# Deckelplatine_v090.net
KiCad netlist of a schematic drawn in EAGLE
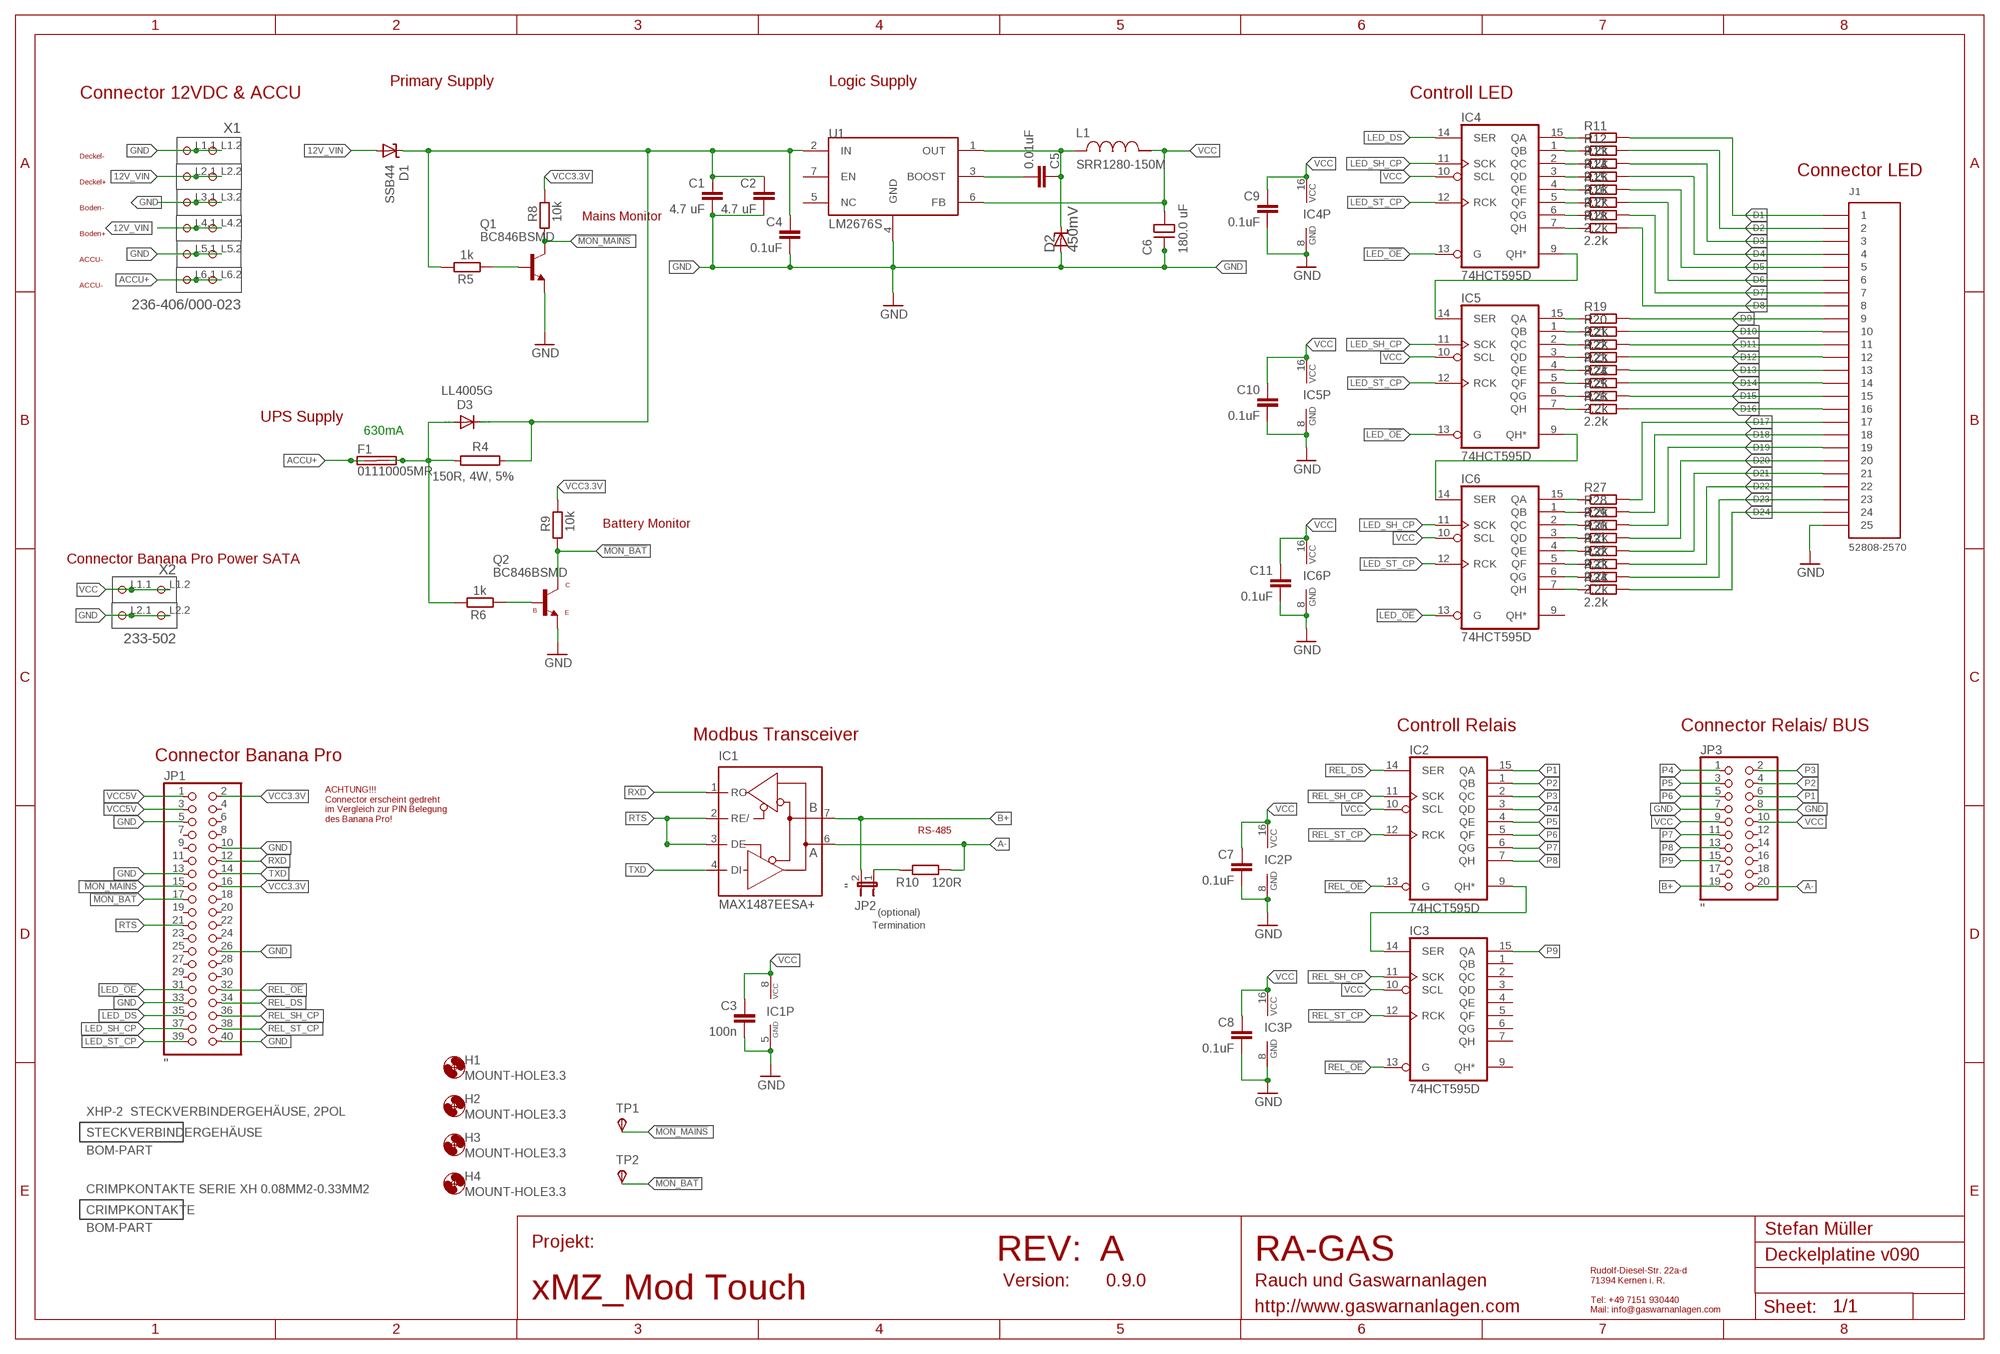
[diagram p0: schematic, sheet 1]

(export (version "E")
  (design (tool "Eeschema 10.0.6"))
  (components
    (comp (ref "C1")
      (value "4.7 uF")
      (footprint "eagle-import:GRM21BR61E475MA12L")
      (fields (field (name "MANUFACTURER_PART_NUMBER") "GRM21BR61E475MA12L") (field (name "MF") "MURATA"))
      (libsource (lib "eagle-import") (part "GRM21BR61E475MA12L"))
    )
    (comp (ref "C2")
      (value "4.7 uF")
      (footprint "eagle-import:GRM21BR61E475MA12L")
      (fields (field (name "MANUFACTURER_PART_NUMBER") "GRM21BR61E475MA12L") (field (name "MF") "MURATA"))
      (libsource (lib "eagle-import") (part "GRM21BR61E475MA12L"))
    )
    (comp (ref "C3")
      (value "100n")
      (footprint "eagle-import:C0603")
      (fields
        (field (name "MF") "KEMET")
        (field (name "MPN") "C0603C104K8RACTU")
        (field (name "PARTNO") "ECHU-16-100N")
      )
      (libsource (lib "eagle-import") (part "C-EUC0603"))
    )
    (comp (ref "C4")
      (value "0.1uF")
      (footprint "eagle-import:0805")
      (fields (field (name "MANUFACTURER_PART_NUMBER") "08053C104KAT2A") (field (name "MF") "AVX"))
      (libsource (lib "eagle-import") (part "08053C104KAT2A"))
    )
    (comp (ref "C5")
      (value "0.01uF")
      (footprint "eagle-import:GRM216R71H103KA01D")
      (fields (field (name "MANUFACTURER_PART_NUMBER") "GRM216R71H103KA01D") (field (name "MF") "MURATA"))
      (libsource (lib "eagle-import") (part "GRM216R71H103KA01D"))
    )
    (comp (ref "C6")
      (value "180.0 uF")
      (footprint "eagle-import:SM_RADIAL_10MM")
      (fields
        (field (name "MF") "PANASONIC ELECTRONIC COMPONENTS")
        (field (name "MPN") "16SVP180MX")
        (field (name "PARTNO") "RAD FC 560/35")
      )
      (libsource (lib "eagle-import") (part "16SVP180MSM_RADIAL_10MM"))
    )
    (comp (ref "C7")
      (value "0.1uF")
      (footprint "eagle-import:C0603")
      (fields
        (field (name "MF") "KEMET")
        (field (name "MPN") "C0603C104K8RACTU")
        (field (name "PARTNO") "SMD TAN.0,1/35")
      )
      (libsource (lib "eagle-import") (part "C-EUC0603"))
    )
    (comp (ref "C8")
      (value "0.1uF")
      (footprint "eagle-import:C0603")
      (fields
        (field (name "MF") "KEMET")
        (field (name "MPN") "C0603C104K8RACTU")
        (field (name "PARTNO") "SMD TAN.0,1/35")
      )
      (libsource (lib "eagle-import") (part "C-EUC0603"))
    )
    (comp (ref "C9")
      (value "0.1uF")
      (footprint "eagle-import:C0603")
      (fields
        (field (name "MF") "KEMET")
        (field (name "MPN") "C0603C104K8RACTU")
        (field (name "PARTNO") "SMD TAN.0,1/35")
      )
      (libsource (lib "eagle-import") (part "C-EUC0603"))
    )
    (comp (ref "C10")
      (value "0.1uF")
      (footprint "eagle-import:C0603")
      (fields
        (field (name "MF") "KEMET")
        (field (name "MPN") "C0603C104K8RACTU")
        (field (name "PARTNO") "SMD TAN.0,1/35")
      )
      (libsource (lib "eagle-import") (part "C-EUC0603"))
    )
    (comp (ref "C11")
      (value "0.1uF")
      (footprint "eagle-import:C0603")
      (fields
        (field (name "MF") "KEMET")
        (field (name "MPN") "C0603C104K8RACTU")
        (field (name "PARTNO") "SMD TAN.0,1/35")
      )
      (libsource (lib "eagle-import") (part "C-EUC0603"))
    )
    (comp (ref "D1")
      (value "SSB44")
      (footprint "eagle-import:SMBJ")
      (fields (field (name "MF") "VISHAY") (field (name "MPN") "SSB44-E3/52T"))
      (libsource (lib "eagle-import") (part "SUPPRESSOR-SMBJ"))
    )
    (comp (ref "D2")
      (value "450mV")
      (footprint "eagle-import:SMB")
      (fields (field (name "MANUFACTURER_PART_NUMBER") "B340LB-13-F") (field (name "MF") "DIODES INC."))
      (libsource (lib "eagle-import") (part "B340LB-13-F"))
    )
    (comp (ref "D3")
      (value "LL4005G")
      (footprint "eagle-import:MELF-MLL41")
      (fields (field (name "MF") "TAIWAN SEMICONDUCTOR"))
      (libsource (lib "eagle-import") (part "DIODE-MELF-MLL41"))
    )
    (comp (ref "F1")
      (value "01110005MR")
      (footprint "eagle-import:01110005MR")
      (fields (field (name "MF") "LITTELFUSE"))
      (libsource (lib "eagle-import") (part "01110005MR"))
    )
    (comp (ref "H1")
      (value "MOUNT-HOLE3.3")
      (footprint "eagle-import:3,3")
      (libsource (lib "eagle-import") (part "MOUNT-HOLE3.3"))
    )
    (comp (ref "H2")
      (value "MOUNT-HOLE3.3")
      (footprint "eagle-import:3,3")
      (libsource (lib "eagle-import") (part "MOUNT-HOLE3.3"))
    )
    (comp (ref "H3")
      (value "MOUNT-HOLE3.3")
      (footprint "eagle-import:3,3")
      (libsource (lib "eagle-import") (part "MOUNT-HOLE3.3"))
    )
    (comp (ref "H4")
      (value "MOUNT-HOLE3.3")
      (footprint "eagle-import:3,3")
      (libsource (lib "eagle-import") (part "MOUNT-HOLE3.3"))
    )
    (comp (ref "IC1")
      (value "MAX1487EESA+")
      (footprint "eagle-import:SO08")
      (fields
        (field (name "MF") "MAXIM")
        (field (name "MPN") "MAX481CSA")
        (field (name "MF_1") "MAXIM INTEGRATED PRODUCTS")
        (field (name "MPN_1") "MAX1487EESA+")
        (field (name "OC_FARNELL") "1593310")
        (field (name "PARTNO") "MAX481CSA")
      )
      (libsource (lib "eagle-import") (part "MAX481CSA"))
    )
    (comp (ref "IC2")
      (value "74HCT595D")
      (footprint "eagle-import:SO16")
      (fields
        (field (name "MF") "NXP")
        (field (name "PARTNO") "SMD HC 595")
        (field (name "MPN") "74HCT595D")
        (field (name "OC_FARNELL") "2098004")
      )
      (libsource (lib "eagle-import") (part "74595DHCT"))
    )
    (comp (ref "IC3")
      (value "74HCT595D")
      (footprint "eagle-import:SO16")
      (fields
        (field (name "MF") "NXP")
        (field (name "MPN") "74HCT595D")
        (field (name "OC_FARNELL") "2098004")
        (field (name "PARTNO") "SMD HC 595")
      )
      (libsource (lib "eagle-import") (part "74595DHCT"))
    )
    (comp (ref "IC4")
      (value "74HCT595D")
      (footprint "eagle-import:SO16")
      (fields
        (field (name "MF") "NXP")
        (field (name "PARTNO") "SMD HC 595")
        (field (name "MPN") "74HCT595D")
        (field (name "OC_FARNELL") "2098004")
      )
      (libsource (lib "eagle-import") (part "74595DHCT"))
    )
    (comp (ref "IC5")
      (value "74HCT595D")
      (footprint "eagle-import:SO16")
      (fields
        (field (name "MF") "NXP")
        (field (name "PARTNO") "SMD HC 595")
        (field (name "MPN") "74HCT595D")
        (field (name "OC_FARNELL") "2098004")
      )
      (libsource (lib "eagle-import") (part "74595DHCT"))
    )
    (comp (ref "IC6")
      (value "74HCT595D")
      (footprint "eagle-import:SO16")
      (fields
        (field (name "MF") "NXP")
        (field (name "PARTNO") "SMD HC 595")
        (field (name "MPN") "74HCT595D")
        (field (name "OC_FARNELL") "2098004")
      )
      (libsource (lib "eagle-import") (part "74595DHCT"))
    )
    (comp (ref "J1")
      (value "52808-2570")
      (footprint "eagle-import:52808-2570")
      (fields (field (name "MF") "MOLEX"))
      (libsource (lib "eagle-import") (part "52808-2570"))
    )
    (comp (ref "JP1")
      (value "''")
      (footprint "eagle-import:2X20")
      (fields (field (name "MF") "HARWIN") (field (name "MPN") "M20-6102045"))
      (libsource (lib "eagle-import") (part "PINHD-2X20"))
    )
    (comp (ref "JP2")
      (value "''")
      (footprint "eagle-import:JP1")
      (fields (field (name "MF") "TE CONNECTIVITY / AMP") (field (name "MPN") "825433-2"))
      (libsource (lib "eagle-import") (part "JP1E"))
    )
    (comp (ref "JP3")
      (value "''")
      (footprint "eagle-import:2X10")
      (fields (field (name "MF") "TE CONNECTIVITY / AMP") (field (name "MPN") "1-1241050-0"))
      (libsource (lib "eagle-import") (part "PINHD-2X10"))
    )
    (comp (ref "L1")
      (value "SRR1280-150M")
      (footprint "eagle-import:SRR1280")
      (fields (field (name "MF") "COILCRAFT") (field (name "MPN") "MSS1278-153MLD"))
      (libsource (lib "eagle-import") (part "SRR1280-150M"))
    )
    (comp (ref "Q1")
      (value "BC846BSMD")
      (footprint "eagle-import:SOT23")
      (fields (field (name "MF") "NXP") (field (name "MPN") "BC846,215"))
      (libsource (lib "eagle-import") (part "BC846SMDB"))
    )
    (comp (ref "Q2")
      (value "BC846BSMD")
      (footprint "eagle-import:SOT23")
      (fields (field (name "MF") "NXP") (field (name "MPN") "BC846,215"))
      (libsource (lib "eagle-import") (part "BC846SMDB"))
    )
    (comp (ref "R4")
      (value "150R, 4W, 5%")
      (footprint "eagle-import:KH206-8")
      (fields
        (field (name "MF") "TE CONNECTIVITY / CGS")
        (field (name "MPN") "ER74150RJT")
        (field (name "OC_FARNELL") "1751842")
      )
      (libsource (lib "eagle-import") (part "RKH206-8"))
    )
    (comp (ref "R5")
      (value "1k")
      (footprint "eagle-import:R1210")
      (fields (field (name "MF") "PANASONIC ELECTRONIC COMPONENTS") (field (name "MPN") "ERJP14F1001U"))
      (libsource (lib "eagle-import") (part "rcl_R-EU_R1210"))
    )
    (comp (ref "R6")
      (value "1k")
      (footprint "eagle-import:R1210")
      (fields (field (name "MF") "PANASONIC ELECTRONIC COMPONENTS") (field (name "MPN") "ERJP14F1001U"))
      (libsource (lib "eagle-import") (part "rcl_R-EU_R1210"))
    )
    (comp (ref "R8")
      (value "10k")
      (footprint "eagle-import:R1210")
      (fields (field (name "MF") "PANASONIC ELECTRONIC COMPONENTS") (field (name "MPN") "ERJP14F1002U"))
      (libsource (lib "eagle-import") (part "rcl_R-EU_R1210"))
    )
    (comp (ref "R9")
      (value "10k")
      (footprint "eagle-import:R1210")
      (fields (field (name "MF") "PANASONIC ELECTRONIC COMPONENTS") (field (name "MPN") "ERJP14F1002U"))
      (libsource (lib "eagle-import") (part "rcl_R-EU_R1210"))
    )
    (comp (ref "R10")
      (value "120R")
      (footprint "eagle-import:R1206")
      (fields (field (name "MF") "TE CONNECTIVITY") (field (name "MPN") "CRGH1206F120R"))
      (libsource (lib "eagle-import") (part "rcl_R-EU_R1206"))
    )
    (comp (ref "R11")
      (value "2.2k")
      (footprint "eagle-import:R0603")
      (fields
        (field (name "MF") "YAGEO (PHYCOMP)")
        (field (name "MPN") "RC0603FR-072K2L")
        (field (name "PARTNO") "SMD-0603 2,2K")
      )
      (libsource (lib "eagle-import") (part "R-EU_R0603"))
    )
    (comp (ref "R12")
      (value "2.2k")
      (footprint "eagle-import:R0603")
      (fields
        (field (name "MF") "YAGEO (PHYCOMP)")
        (field (name "MPN") "RC0603FR-072K2L")
        (field (name "PARTNO") "SMD-0603 2,2K")
      )
      (libsource (lib "eagle-import") (part "R-EU_R0603"))
    )
    (comp (ref "R13")
      (value "2.2k")
      (footprint "eagle-import:R0603")
      (fields
        (field (name "MF") "YAGEO (PHYCOMP)")
        (field (name "MPN") "RC0603FR-072K2L")
        (field (name "PARTNO") "SMD-0603 2,2K")
      )
      (libsource (lib "eagle-import") (part "R-EU_R0603"))
    )
    (comp (ref "R14")
      (value "2.2k")
      (footprint "eagle-import:R0603")
      (fields
        (field (name "MF") "YAGEO (PHYCOMP)")
        (field (name "MPN") "RC0603FR-072K2L")
        (field (name "PARTNO") "SMD-0603 2,2K")
      )
      (libsource (lib "eagle-import") (part "R-EU_R0603"))
    )
    (comp (ref "R15")
      (value "2.2k")
      (footprint "eagle-import:R0603")
      (fields
        (field (name "MF") "YAGEO (PHYCOMP)")
        (field (name "MPN") "RC0603FR-072K2L")
        (field (name "PARTNO") "SMD-0603 2,2K")
      )
      (libsource (lib "eagle-import") (part "R-EU_R0603"))
    )
    (comp (ref "R16")
      (value "2.2k")
      (footprint "eagle-import:R0603")
      (fields
        (field (name "MF") "YAGEO (PHYCOMP)")
        (field (name "MPN") "RC0603FR-072K2L")
        (field (name "PARTNO") "SMD-0603 2,2K")
      )
      (libsource (lib "eagle-import") (part "R-EU_R0603"))
    )
    (comp (ref "R17")
      (value "2.2k")
      (footprint "eagle-import:R0603")
      (fields
        (field (name "MF") "YAGEO (PHYCOMP)")
        (field (name "MPN") "RC0603FR-072K2L")
        (field (name "PARTNO") "SMD-0603 2,2K")
      )
      (libsource (lib "eagle-import") (part "R-EU_R0603"))
    )
    (comp (ref "R18")
      (value "2.2k")
      (footprint "eagle-import:R0603")
      (fields
        (field (name "MF") "YAGEO (PHYCOMP)")
        (field (name "MPN") "RC0603FR-072K2L")
        (field (name "PARTNO") "SMD-0603 2,2K")
      )
      (libsource (lib "eagle-import") (part "R-EU_R0603"))
    )
    (comp (ref "R19")
      (value "2.2k")
      (footprint "eagle-import:R0603")
      (fields
        (field (name "MF") "YAGEO (PHYCOMP)")
        (field (name "MPN") "RC0603FR-072K2L")
        (field (name "PARTNO") "SMD-0603 2,2K")
      )
      (libsource (lib "eagle-import") (part "R-EU_R0603"))
    )
    (comp (ref "R20")
      (value "2.2k")
      (footprint "eagle-import:R0603")
      (fields
        (field (name "MF") "YAGEO (PHYCOMP)")
        (field (name "MPN") "RC0603FR-072K2L")
        (field (name "PARTNO") "SMD-0603 2,2K")
      )
      (libsource (lib "eagle-import") (part "R-EU_R0603"))
    )
    (comp (ref "R21")
      (value "2.2k")
      (footprint "eagle-import:R0603")
      (fields
        (field (name "MF") "YAGEO (PHYCOMP)")
        (field (name "MPN") "RC0603FR-072K2L")
        (field (name "PARTNO") "SMD-0603 2,2K")
      )
      (libsource (lib "eagle-import") (part "R-EU_R0603"))
    )
    (comp (ref "R22")
      (value "2.2k")
      (footprint "eagle-import:R0603")
      (fields
        (field (name "MF") "YAGEO (PHYCOMP)")
        (field (name "MPN") "RC0603FR-072K2L")
        (field (name "PARTNO") "SMD-0603 2,2K")
      )
      (libsource (lib "eagle-import") (part "R-EU_R0603"))
    )
    (comp (ref "R23")
      (value "2.2k")
      (footprint "eagle-import:R0603")
      (fields
        (field (name "MF") "YAGEO (PHYCOMP)")
        (field (name "MPN") "RC0603FR-072K2L")
        (field (name "PARTNO") "SMD-0603 2,2K")
      )
      (libsource (lib "eagle-import") (part "R-EU_R0603"))
    )
    (comp (ref "R24")
      (value "2.2k")
      (footprint "eagle-import:R0603")
      (fields
        (field (name "MF") "YAGEO (PHYCOMP)")
        (field (name "MPN") "RC0603FR-072K2L")
        (field (name "PARTNO") "SMD-0603 2,2K")
      )
      (libsource (lib "eagle-import") (part "R-EU_R0603"))
    )
    (comp (ref "R25")
      (value "2.2k")
      (footprint "eagle-import:R0603")
      (fields
        (field (name "MF") "YAGEO (PHYCOMP)")
        (field (name "MPN") "RC0603FR-072K2L")
        (field (name "PARTNO") "SMD-0603 2,2K")
      )
      (libsource (lib "eagle-import") (part "R-EU_R0603"))
    )
    (comp (ref "R26")
      (value "2.2k")
      (footprint "eagle-import:R0603")
      (fields
        (field (name "MF") "YAGEO (PHYCOMP)")
        (field (name "MPN") "RC0603FR-072K2L")
        (field (name "PARTNO") "SMD-0603 2,2K")
      )
      (libsource (lib "eagle-import") (part "R-EU_R0603"))
    )
    (comp (ref "R27")
      (value "2.2k")
      (footprint "eagle-import:R0603")
      (fields
        (field (name "MF") "YAGEO (PHYCOMP)")
        (field (name "MPN") "RC0603FR-072K2L")
        (field (name "PARTNO") "SMD-0603 2,2K")
      )
      (libsource (lib "eagle-import") (part "R-EU_R0603"))
    )
    (comp (ref "R28")
      (value "2.2k")
      (footprint "eagle-import:R0603")
      (fields
        (field (name "MF") "YAGEO (PHYCOMP)")
        (field (name "MPN") "RC0603FR-072K2L")
        (field (name "PARTNO") "SMD-0603 2,2K")
      )
      (libsource (lib "eagle-import") (part "R-EU_R0603"))
    )
    (comp (ref "R29")
      (value "2.2k")
      (footprint "eagle-import:R0603")
      (fields
        (field (name "MF") "YAGEO (PHYCOMP)")
        (field (name "MPN") "RC0603FR-072K2L")
        (field (name "PARTNO") "SMD-0603 2,2K")
      )
      (libsource (lib "eagle-import") (part "R-EU_R0603"))
    )
    (comp (ref "R30")
      (value "2.2k")
      (footprint "eagle-import:R0603")
      (fields
        (field (name "MF") "YAGEO (PHYCOMP)")
        (field (name "MPN") "RC0603FR-072K2L")
        (field (name "PARTNO") "SMD-0603 2,2K")
      )
      (libsource (lib "eagle-import") (part "R-EU_R0603"))
    )
    (comp (ref "R31")
      (value "2.2k")
      (footprint "eagle-import:R0603")
      (fields
        (field (name "MF") "YAGEO (PHYCOMP)")
        (field (name "MPN") "RC0603FR-072K2L")
        (field (name "PARTNO") "SMD-0603 2,2K")
      )
      (libsource (lib "eagle-import") (part "R-EU_R0603"))
    )
    (comp (ref "R32")
      (value "2.2k")
      (footprint "eagle-import:R0603")
      (fields
        (field (name "MF") "YAGEO (PHYCOMP)")
        (field (name "MPN") "RC0603FR-072K2L")
        (field (name "PARTNO") "SMD-0603 2,2K")
      )
      (libsource (lib "eagle-import") (part "R-EU_R0603"))
    )
    (comp (ref "R33")
      (value "2.2k")
      (footprint "eagle-import:R0603")
      (fields
        (field (name "MF") "YAGEO (PHYCOMP)")
        (field (name "MPN") "RC0603FR-072K2L")
        (field (name "PARTNO") "SMD-0603 2,2K")
      )
      (libsource (lib "eagle-import") (part "R-EU_R0603"))
    )
    (comp (ref "R34")
      (value "2.2k")
      (footprint "eagle-import:R0603")
      (fields
        (field (name "MF") "YAGEO (PHYCOMP)")
        (field (name "MPN") "RC0603FR-072K2L")
        (field (name "PARTNO") "SMD-0603 2,2K")
      )
      (libsource (lib "eagle-import") (part "R-EU_R0603"))
    )
    (comp (ref "TP1")
      (value "TPSB1,27")
      (footprint "eagle-import:B1,27")
      (libsource (lib "eagle-import") (part "TPSB1,27"))
    )
    (comp (ref "TP2")
      (value "TPSB1,27")
      (footprint "eagle-import:B1,27")
      (libsource (lib "eagle-import") (part "TPSB1,27"))
    )
    (comp (ref "U1")
      (value "LM2676S")
      (footprint "eagle-import:TO-263-7")
      (fields (field (name "MF") "TEXAS INSTRUMENTS") (field (name "MPN") "LM2676SX-5.0/NOPB"))
      (libsource (lib "eagle-import") (part "LM2676S"))
    )
    (comp (ref "X1")
      (value "236-406/000-023")
      (footprint "eagle-import:P-236-406")
      (fields (field (name "MF") "WAGO") (field (name "MPN") "236-406"))
      (libsource (lib "eagle-import") (part "236-406/000-023"))
    )
    (comp (ref "X2")
      (value "233-502")
      (footprint "eagle-import:P-233-502")
      (fields (field (name "MF") "WAGO") (field (name "MPN") "233-502."))
      (libsource (lib "eagle-import") (part "233-502"))
    )
  )
  (nets
    (net (code "1") (name "/LED_~{OE}") (class "Default")
      (node (ref "IC4") (pin "13") (pinfunction "G_13") (pintype "input"))
      (node (ref "IC5") (pin "13") (pinfunction "G_13") (pintype "input"))
      (node (ref "IC6") (pin "13") (pinfunction "G_13") (pintype "input"))
      (node (ref "JP1") (pin "31") (pinfunction "31_31") (pintype "passive"))
    )
    (net (code "2") (name "/REL_~{OE}") (class "Default")
      (node (ref "IC2") (pin "13") (pinfunction "G_13") (pintype "input"))
      (node (ref "IC3") (pin "13") (pinfunction "G_13") (pintype "input"))
      (node (ref "JP1") (pin "32") (pinfunction "32_32") (pintype "passive"))
    )
    (net (code "3") (name "/~{MON_BAT}") (class "Default")
      (node (ref "JP1") (pin "17") (pinfunction "17_17") (pintype "passive"))
      (node (ref "Q2") (pin "3") (pinfunction "C_3") (pintype "passive"))
      (node (ref "R9") (pin "1") (pinfunction "1_1") (pintype "passive"))
      (node (ref "TP2") (pin "TP") (pinfunction "PP_TP") (pintype "input"))
    )
    (net (code "4") (name "/~{MON_MAINS}") (class "Default")
      (node (ref "JP1") (pin "15") (pinfunction "15_15") (pintype "passive"))
      (node (ref "Q1") (pin "3") (pinfunction "C_3") (pintype "passive"))
      (node (ref "R8") (pin "1") (pinfunction "1_1") (pintype "passive"))
      (node (ref "TP1") (pin "TP") (pinfunction "PP_TP") (pintype "input"))
    )
    (net (code "5") (name "12V_VIN") (class "Default")
      (node (ref "C1") (pin "1") (pinfunction "1_1") (pintype "passive"))
      (node (ref "C2") (pin "1") (pinfunction "1_1") (pintype "passive"))
      (node (ref "C4") (pin "1") (pinfunction "1_1") (pintype "passive"))
      (node (ref "D1") (pin "A") (pinfunction "A_A") (pintype "passive"))
      (node (ref "D1") (pin "C") (pinfunction "C_C") (pintype "passive"))
      (node (ref "D3") (pin "C") (pinfunction "C_C") (pintype "passive"))
      (node (ref "R4") (pin "2") (pinfunction "2_2") (pintype "passive"))
      (node (ref "R5") (pin "2") (pinfunction "2_2") (pintype "passive"))
      (node (ref "U1") (pin "2") (pinfunction "IN_2") (pintype "power_in"))
      (node (ref "X1") (pin "L2.1") (pinfunction "P2.1_L2.1") (pintype "bidirectional"))
      (node (ref "X1") (pin "L2.2") (pinfunction "P2.2_L2.2") (pintype "bidirectional"))
      (node (ref "X1") (pin "L4.1") (pinfunction "P4.1_L4.1") (pintype "bidirectional"))
      (node (ref "X1") (pin "L4.2") (pinfunction "P4.2_L4.2") (pintype "bidirectional"))
    )
    (net (code "6") (name "A-") (class "Default")
      (node (ref "IC1") (pin "6") (pinfunction "A_6") (pintype "passive"))
      (node (ref "JP3") (pin "20") (pinfunction "20_20") (pintype "passive"))
      (node (ref "R10") (pin "2") (pinfunction "2_2") (pintype "passive"))
    )
    (net (code "7") (name "ACCU+") (class "Default")
      (node (ref "D3") (pin "A") (pinfunction "A_A") (pintype "passive"))
      (node (ref "F1") (pin "1A") (pinfunction "1A_1A") (pintype "passive"))
      (node (ref "F1") (pin "1B") (pinfunction "1B_1B") (pintype "passive"))
      (node (ref "F1") (pin "2A") (pinfunction "2A_2A") (pintype "passive"))
      (node (ref "F1") (pin "2B") (pinfunction "2B_2B") (pintype "passive"))
      (node (ref "R4") (pin "1") (pinfunction "1_1") (pintype "passive"))
      (node (ref "R6") (pin "2") (pinfunction "2_2") (pintype "passive"))
      (node (ref "X1") (pin "L6.1") (pinfunction "P6.1_L6.1") (pintype "bidirectional"))
      (node (ref "X1") (pin "L6.2") (pinfunction "P6.2_L6.2") (pintype "bidirectional"))
    )
    (net (code "8") (name "B+") (class "Default")
      (node (ref "IC1") (pin "7") (pinfunction "B_7") (pintype "passive"))
      (node (ref "JP2") (pin "2") (pinfunction "2_2") (pintype "passive"))
      (node (ref "JP3") (pin "19") (pinfunction "19_19") (pintype "passive"))
    )
    (net (code "9") (name "D1") (class "Default")
      (node (ref "J1") (pin "1") (pinfunction "1_1") (pintype "bidirectional"))
      (node (ref "R11") (pin "2") (pinfunction "2_2") (pintype "passive"))
    )
    (net (code "10") (name "D2") (class "Default")
      (node (ref "J1") (pin "2") (pinfunction "2_2") (pintype "bidirectional"))
      (node (ref "R12") (pin "2") (pinfunction "2_2") (pintype "passive"))
    )
    (net (code "11") (name "D3") (class "Default")
      (node (ref "J1") (pin "3") (pinfunction "3_3") (pintype "bidirectional"))
      (node (ref "R13") (pin "2") (pinfunction "2_2") (pintype "passive"))
    )
    (net (code "12") (name "D4") (class "Default")
      (node (ref "J1") (pin "4") (pinfunction "4_4") (pintype "bidirectional"))
      (node (ref "R14") (pin "2") (pinfunction "2_2") (pintype "passive"))
    )
    (net (code "13") (name "D5") (class "Default")
      (node (ref "J1") (pin "5") (pinfunction "5_5") (pintype "bidirectional"))
      (node (ref "R15") (pin "2") (pinfunction "2_2") (pintype "passive"))
    )
    (net (code "14") (name "D6") (class "Default")
      (node (ref "J1") (pin "6") (pinfunction "6_6") (pintype "bidirectional"))
      (node (ref "R16") (pin "2") (pinfunction "2_2") (pintype "passive"))
    )
    (net (code "15") (name "D7") (class "Default")
      (node (ref "J1") (pin "7") (pinfunction "7_7") (pintype "bidirectional"))
      (node (ref "R17") (pin "2") (pinfunction "2_2") (pintype "passive"))
    )
    (net (code "16") (name "D8") (class "Default")
      (node (ref "J1") (pin "8") (pinfunction "8_8") (pintype "bidirectional"))
      (node (ref "R18") (pin "2") (pinfunction "2_2") (pintype "passive"))
    )
    (net (code "17") (name "D9") (class "Default")
      (node (ref "J1") (pin "9") (pinfunction "9_9") (pintype "bidirectional"))
      (node (ref "R19") (pin "2") (pinfunction "2_2") (pintype "passive"))
    )
    (net (code "18") (name "D10") (class "Default")
      (node (ref "J1") (pin "10") (pinfunction "10_10") (pintype "bidirectional"))
      (node (ref "R20") (pin "2") (pinfunction "2_2") (pintype "passive"))
    )
    (net (code "19") (name "D11") (class "Default")
      (node (ref "J1") (pin "11") (pinfunction "11_11") (pintype "bidirectional"))
      (node (ref "R21") (pin "2") (pinfunction "2_2") (pintype "passive"))
    )
    (net (code "20") (name "D12") (class "Default")
      (node (ref "J1") (pin "12") (pinfunction "12_12") (pintype "bidirectional"))
      (node (ref "R22") (pin "2") (pinfunction "2_2") (pintype "passive"))
    )
    (net (code "21") (name "D13") (class "Default")
      (node (ref "J1") (pin "13") (pinfunction "13_13") (pintype "bidirectional"))
      (node (ref "R23") (pin "2") (pinfunction "2_2") (pintype "passive"))
    )
    (net (code "22") (name "D14") (class "Default")
      (node (ref "J1") (pin "14") (pinfunction "14_14") (pintype "bidirectional"))
      (node (ref "R24") (pin "2") (pinfunction "2_2") (pintype "passive"))
    )
    (net (code "23") (name "D15") (class "Default")
      (node (ref "J1") (pin "15") (pinfunction "15_15") (pintype "bidirectional"))
      (node (ref "R25") (pin "2") (pinfunction "2_2") (pintype "passive"))
    )
    (net (code "24") (name "D16") (class "Default")
      (node (ref "J1") (pin "16") (pinfunction "16_16") (pintype "bidirectional"))
      (node (ref "R26") (pin "2") (pinfunction "2_2") (pintype "passive"))
    )
    (net (code "25") (name "D17") (class "Default")
      (node (ref "J1") (pin "17") (pinfunction "17_17") (pintype "bidirectional"))
      (node (ref "R27") (pin "2") (pinfunction "2_2") (pintype "passive"))
    )
    (net (code "26") (name "D18") (class "Default")
      (node (ref "J1") (pin "18") (pinfunction "18_18") (pintype "bidirectional"))
      (node (ref "R28") (pin "2") (pinfunction "2_2") (pintype "passive"))
    )
    (net (code "27") (name "D19") (class "Default")
      (node (ref "J1") (pin "19") (pinfunction "19_19") (pintype "bidirectional"))
      (node (ref "R29") (pin "2") (pinfunction "2_2") (pintype "passive"))
    )
    (net (code "28") (name "D20") (class "Default")
      (node (ref "J1") (pin "20") (pinfunction "20_20") (pintype "bidirectional"))
      (node (ref "R30") (pin "2") (pinfunction "2_2") (pintype "passive"))
    )
    (net (code "29") (name "D21") (class "Default")
      (node (ref "J1") (pin "21") (pinfunction "21_21") (pintype "bidirectional"))
      (node (ref "R31") (pin "2") (pinfunction "2_2") (pintype "passive"))
    )
    (net (code "30") (name "D22") (class "Default")
      (node (ref "J1") (pin "22") (pinfunction "22_22") (pintype "bidirectional"))
      (node (ref "R32") (pin "2") (pinfunction "2_2") (pintype "passive"))
    )
    (net (code "31") (name "D23") (class "Default")
      (node (ref "J1") (pin "23") (pinfunction "23_23") (pintype "bidirectional"))
      (node (ref "R33") (pin "2") (pinfunction "2_2") (pintype "passive"))
    )
    (net (code "32") (name "D24") (class "Default")
      (node (ref "J1") (pin "24") (pinfunction "24_24") (pintype "bidirectional"))
      (node (ref "R34") (pin "2") (pinfunction "2_2") (pintype "passive"))
    )
    (net (code "33") (name "GND") (class "Default")
      (node (ref "C1") (pin "2") (pinfunction "2_2") (pintype "passive"))
      (node (ref "C10") (pin "2") (pinfunction "2_2") (pintype "passive"))
      (node (ref "C11") (pin "2") (pinfunction "2_2") (pintype "passive"))
      (node (ref "C2") (pin "2") (pinfunction "2_2") (pintype "passive"))
      (node (ref "C3") (pin "2") (pinfunction "2_2") (pintype "passive"))
      (node (ref "C4") (pin "2") (pinfunction "2_2") (pintype "passive"))
      (node (ref "C6") (pin "2") (pinfunction "-_2") (pintype "passive"))
      (node (ref "C7") (pin "2") (pinfunction "2_2") (pintype "passive"))
      (node (ref "C8") (pin "2") (pinfunction "2_2") (pintype "passive"))
      (node (ref "C9") (pin "2") (pinfunction "2_2") (pintype "passive"))
      (node (ref "D2") (pin "A") (pinfunction "A_A") (pintype "passive"))
      (node (ref "IC1") (pin "5") (pinfunction "GND_5") (pintype "power_in"))
      (node (ref "IC2") (pin "8") (pinfunction "GND_8") (pintype "power_in"))
      (node (ref "IC3") (pin "8") (pinfunction "GND_8") (pintype "power_in"))
      (node (ref "IC4") (pin "8") (pinfunction "GND_8") (pintype "power_in"))
      (node (ref "IC5") (pin "8") (pinfunction "GND_8") (pintype "power_in"))
      (node (ref "IC6") (pin "8") (pinfunction "GND_8") (pintype "power_in"))
      (node (ref "J1") (pin "25") (pinfunction "25_25") (pintype "bidirectional"))
      (node (ref "JP1") (pin "10") (pinfunction "10_10") (pintype "passive"))
      (node (ref "JP1") (pin "13") (pinfunction "13_13") (pintype "passive"))
      (node (ref "JP1") (pin "26") (pinfunction "26_26") (pintype "passive"))
      (node (ref "JP1") (pin "33") (pinfunction "33_33") (pintype "passive"))
      (node (ref "JP1") (pin "40") (pinfunction "40_40") (pintype "passive"))
      (node (ref "JP1") (pin "5") (pinfunction "5_5") (pintype "passive"))
      (node (ref "JP3") (pin "7") (pinfunction "7_7") (pintype "passive"))
      (node (ref "JP3") (pin "8") (pinfunction "8_8") (pintype "passive"))
      (node (ref "Q1") (pin "2") (pinfunction "E_2") (pintype "passive"))
      (node (ref "Q2") (pin "2") (pinfunction "E_2") (pintype "passive"))
      (node (ref "U1") (pin "4") (pinfunction "GND_4") (pintype "power_in"))
      (node (ref "X1") (pin "L1.1") (pinfunction "P1.1_L1.1") (pintype "bidirectional"))
      (node (ref "X1") (pin "L1.2") (pinfunction "P1.2_L1.2") (pintype "bidirectional"))
      (node (ref "X1") (pin "L3.1") (pinfunction "P3.1_L3.1") (pintype "bidirectional"))
      (node (ref "X1") (pin "L3.2") (pinfunction "P3.2_L3.2") (pintype "bidirectional"))
      (node (ref "X1") (pin "L5.1") (pinfunction "P5.1_L5.1") (pintype "bidirectional"))
      (node (ref "X1") (pin "L5.2") (pinfunction "P5.2_L5.2") (pintype "bidirectional"))
      (node (ref "X2") (pin "L2.1") (pinfunction "P2.1_L2.1") (pintype "bidirectional"))
      (node (ref "X2") (pin "L2.2") (pinfunction "P2.2_L2.2") (pintype "bidirectional"))
    )
    (net (code "34") (name "LED_DS") (class "Default")
      (node (ref "IC4") (pin "14") (pinfunction "SER_14") (pintype "input"))
      (node (ref "JP1") (pin "35") (pinfunction "35_35") (pintype "passive"))
    )
    (net (code "35") (name "LED_SH_CP") (class "Default")
      (node (ref "IC4") (pin "11") (pinfunction "SCK_11") (pintype "input"))
      (node (ref "IC5") (pin "11") (pinfunction "SCK_11") (pintype "input"))
      (node (ref "IC6") (pin "11") (pinfunction "SCK_11") (pintype "input"))
      (node (ref "JP1") (pin "37") (pinfunction "37_37") (pintype "passive"))
    )
    (net (code "36") (name "LED_ST_CP") (class "Default")
      (node (ref "IC4") (pin "12") (pinfunction "RCK_12") (pintype "input"))
      (node (ref "IC5") (pin "12") (pinfunction "RCK_12") (pintype "input"))
      (node (ref "IC6") (pin "12") (pinfunction "RCK_12") (pintype "input"))
      (node (ref "JP1") (pin "39") (pinfunction "39_39") (pintype "passive"))
    )
    (net (code "37") (name "Net-(IC2A-QH*)") (class "Default")
      (node (ref "IC2") (pin "9") (pinfunction "QH*_9") (pintype "tri_state"))
      (node (ref "IC3") (pin "14") (pinfunction "SER_14") (pintype "input"))
    )
    (net (code "38") (name "Net-(IC4A-QA)") (class "Default")
      (node (ref "IC4") (pin "15") (pinfunction "QA_15") (pintype "tri_state"))
      (node (ref "R11") (pin "1") (pinfunction "1_1") (pintype "passive"))
    )
    (net (code "39") (name "Net-(IC4A-QB)") (class "Default")
      (node (ref "IC4") (pin "1") (pinfunction "QB_1") (pintype "tri_state"))
      (node (ref "R12") (pin "1") (pinfunction "1_1") (pintype "passive"))
    )
    (net (code "40") (name "Net-(IC4A-QC)") (class "Default")
      (node (ref "IC4") (pin "2") (pinfunction "QC_2") (pintype "tri_state"))
      (node (ref "R13") (pin "1") (pinfunction "1_1") (pintype "passive"))
    )
    (net (code "41") (name "Net-(IC4A-QD)") (class "Default")
      (node (ref "IC4") (pin "3") (pinfunction "QD_3") (pintype "tri_state"))
      (node (ref "R14") (pin "1") (pinfunction "1_1") (pintype "passive"))
    )
    (net (code "42") (name "Net-(IC4A-QE)") (class "Default")
      (node (ref "IC4") (pin "4") (pinfunction "QE_4") (pintype "tri_state"))
      (node (ref "R15") (pin "1") (pinfunction "1_1") (pintype "passive"))
    )
    (net (code "43") (name "Net-(IC4A-QF)") (class "Default")
      (node (ref "IC4") (pin "5") (pinfunction "QF_5") (pintype "tri_state"))
      (node (ref "R16") (pin "1") (pinfunction "1_1") (pintype "passive"))
    )
    (net (code "44") (name "Net-(IC4A-QG)") (class "Default")
      (node (ref "IC4") (pin "6") (pinfunction "QG_6") (pintype "tri_state"))
      (node (ref "R17") (pin "1") (pinfunction "1_1") (pintype "passive"))
    )
    (net (code "45") (name "Net-(IC4A-QH)") (class "Default")
      (node (ref "IC4") (pin "7") (pinfunction "QH_7") (pintype "tri_state"))
      (node (ref "R18") (pin "1") (pinfunction "1_1") (pintype "passive"))
    )
    (net (code "46") (name "Net-(IC4A-QH*)") (class "Default")
      (node (ref "IC4") (pin "9") (pinfunction "QH*_9") (pintype "tri_state"))
      (node (ref "IC5") (pin "14") (pinfunction "SER_14") (pintype "input"))
    )
    (net (code "47") (name "Net-(IC5A-QA)") (class "Default")
      (node (ref "IC5") (pin "15") (pinfunction "QA_15") (pintype "tri_state"))
      (node (ref "R19") (pin "1") (pinfunction "1_1") (pintype "passive"))
    )
    (net (code "48") (name "Net-(IC5A-QB)") (class "Default")
      (node (ref "IC5") (pin "1") (pinfunction "QB_1") (pintype "tri_state"))
      (node (ref "R20") (pin "1") (pinfunction "1_1") (pintype "passive"))
    )
    (net (code "49") (name "Net-(IC5A-QC)") (class "Default")
      (node (ref "IC5") (pin "2") (pinfunction "QC_2") (pintype "tri_state"))
      (node (ref "R21") (pin "1") (pinfunction "1_1") (pintype "passive"))
    )
    (net (code "50") (name "Net-(IC5A-QD)") (class "Default")
      (node (ref "IC5") (pin "3") (pinfunction "QD_3") (pintype "tri_state"))
      (node (ref "R22") (pin "1") (pinfunction "1_1") (pintype "passive"))
    )
    (net (code "51") (name "Net-(IC5A-QE)") (class "Default")
      (node (ref "IC5") (pin "4") (pinfunction "QE_4") (pintype "tri_state"))
      (node (ref "R23") (pin "1") (pinfunction "1_1") (pintype "passive"))
    )
    (net (code "52") (name "Net-(IC5A-QF)") (class "Default")
      (node (ref "IC5") (pin "5") (pinfunction "QF_5") (pintype "tri_state"))
      (node (ref "R24") (pin "1") (pinfunction "1_1") (pintype "passive"))
    )
    (net (code "53") (name "Net-(IC5A-QG)") (class "Default")
      (node (ref "IC5") (pin "6") (pinfunction "QG_6") (pintype "tri_state"))
      (node (ref "R25") (pin "1") (pinfunction "1_1") (pintype "passive"))
    )
    (net (code "54") (name "Net-(IC5A-QH)") (class "Default")
      (node (ref "IC5") (pin "7") (pinfunction "QH_7") (pintype "tri_state"))
      (node (ref "R26") (pin "1") (pinfunction "1_1") (pintype "passive"))
    )
    (net (code "55") (name "Net-(IC5A-QH*)") (class "Default")
      (node (ref "IC5") (pin "9") (pinfunction "QH*_9") (pintype "tri_state"))
      (node (ref "IC6") (pin "14") (pinfunction "SER_14") (pintype "input"))
    )
    (net (code "56") (name "Net-(IC6A-QA)") (class "Default")
      (node (ref "IC6") (pin "15") (pinfunction "QA_15") (pintype "tri_state"))
      (node (ref "R27") (pin "1") (pinfunction "1_1") (pintype "passive"))
    )
    (net (code "57") (name "Net-(IC6A-QB)") (class "Default")
      (node (ref "IC6") (pin "1") (pinfunction "QB_1") (pintype "tri_state"))
      (node (ref "R28") (pin "1") (pinfunction "1_1") (pintype "passive"))
    )
    (net (code "58") (name "Net-(IC6A-QC)") (class "Default")
      (node (ref "IC6") (pin "2") (pinfunction "QC_2") (pintype "tri_state"))
      (node (ref "R29") (pin "1") (pinfunction "1_1") (pintype "passive"))
    )
    (net (code "59") (name "Net-(IC6A-QD)") (class "Default")
      (node (ref "IC6") (pin "3") (pinfunction "QD_3") (pintype "tri_state"))
      (node (ref "R30") (pin "1") (pinfunction "1_1") (pintype "passive"))
    )
    (net (code "60") (name "Net-(IC6A-QE)") (class "Default")
      (node (ref "IC6") (pin "4") (pinfunction "QE_4") (pintype "tri_state"))
      (node (ref "R31") (pin "1") (pinfunction "1_1") (pintype "passive"))
    )
    (net (code "61") (name "Net-(IC6A-QF)") (class "Default")
      (node (ref "IC6") (pin "5") (pinfunction "QF_5") (pintype "tri_state"))
      (node (ref "R32") (pin "1") (pinfunction "1_1") (pintype "passive"))
    )
    (net (code "62") (name "Net-(IC6A-QG)") (class "Default")
      (node (ref "IC6") (pin "6") (pinfunction "QG_6") (pintype "tri_state"))
      (node (ref "R33") (pin "1") (pinfunction "1_1") (pintype "passive"))
    )
    (net (code "63") (name "Net-(IC6A-QH)") (class "Default")
      (node (ref "IC6") (pin "7") (pinfunction "QH_7") (pintype "tri_state"))
      (node (ref "R34") (pin "1") (pinfunction "1_1") (pintype "passive"))
    )
    (net (code "64") (name "Net-(JP2-Pad1)") (class "Default")
      (node (ref "JP2") (pin "1") (pinfunction "1_1") (pintype "passive"))
      (node (ref "R10") (pin "1") (pinfunction "1_1") (pintype "passive"))
    )
    (net (code "65") (name "Net-(Q1-B)") (class "Default")
      (node (ref "Q1") (pin "1") (pinfunction "B_1") (pintype "passive"))
      (node (ref "R5") (pin "1") (pinfunction "1_1") (pintype "passive"))
    )
    (net (code "66") (name "Net-(Q2-B)") (class "Default")
      (node (ref "Q2") (pin "1") (pinfunction "B_1") (pintype "passive"))
      (node (ref "R6") (pin "1") (pinfunction "1_1") (pintype "passive"))
    )
    (net (code "67") (name "Net-(U1-BOOST)") (class "Default")
      (node (ref "C5") (pin "2") (pinfunction "2_2") (pintype "passive"))
      (node (ref "U1") (pin "3") (pinfunction "BOOST_3") (pintype "bidirectional"))
    )
    (net (code "68") (name "Net-(U1-OUT)") (class "Default")
      (node (ref "C5") (pin "1") (pinfunction "1_1") (pintype "passive"))
      (node (ref "D2") (pin "C") (pinfunction "C_C") (pintype "passive"))
      (node (ref "L1") (pin "1") (pinfunction "1_1") (pintype "passive"))
      (node (ref "U1") (pin "1") (pinfunction "OUT_1") (pintype "bidirectional"))
    )
    (net (code "69") (name "P1") (class "Default")
      (node (ref "IC2") (pin "15") (pinfunction "QA_15") (pintype "tri_state"))
      (node (ref "JP3") (pin "6") (pinfunction "6_6") (pintype "passive"))
    )
    (net (code "70") (name "P2") (class "Default")
      (node (ref "IC2") (pin "1") (pinfunction "QB_1") (pintype "tri_state"))
      (node (ref "JP3") (pin "4") (pinfunction "4_4") (pintype "passive"))
    )
    (net (code "71") (name "P3") (class "Default")
      (node (ref "IC2") (pin "2") (pinfunction "QC_2") (pintype "tri_state"))
      (node (ref "JP3") (pin "2") (pinfunction "2_2") (pintype "passive"))
    )
    (net (code "72") (name "P4") (class "Default")
      (node (ref "IC2") (pin "3") (pinfunction "QD_3") (pintype "tri_state"))
      (node (ref "JP3") (pin "1") (pinfunction "1_1") (pintype "passive"))
    )
    (net (code "73") (name "P5") (class "Default")
      (node (ref "IC2") (pin "4") (pinfunction "QE_4") (pintype "tri_state"))
      (node (ref "JP3") (pin "3") (pinfunction "3_3") (pintype "passive"))
    )
    (net (code "74") (name "P6") (class "Default")
      (node (ref "IC2") (pin "5") (pinfunction "QF_5") (pintype "tri_state"))
      (node (ref "JP3") (pin "5") (pinfunction "5_5") (pintype "passive"))
    )
    (net (code "75") (name "P7") (class "Default")
      (node (ref "IC2") (pin "6") (pinfunction "QG_6") (pintype "tri_state"))
      (node (ref "JP3") (pin "11") (pinfunction "11_11") (pintype "passive"))
    )
    (net (code "76") (name "P8") (class "Default")
      (node (ref "IC2") (pin "7") (pinfunction "QH_7") (pintype "tri_state"))
      (node (ref "JP3") (pin "13") (pinfunction "13_13") (pintype "passive"))
    )
    (net (code "77") (name "P9") (class "Default")
      (node (ref "IC3") (pin "15") (pinfunction "QA_15") (pintype "tri_state"))
      (node (ref "JP3") (pin "15") (pinfunction "15_15") (pintype "passive"))
    )
    (net (code "78") (name "REL_DS") (class "Default")
      (node (ref "IC2") (pin "14") (pinfunction "SER_14") (pintype "input"))
      (node (ref "JP1") (pin "34") (pinfunction "34_34") (pintype "passive"))
    )
    (net (code "79") (name "REL_SH_CP") (class "Default")
      (node (ref "IC2") (pin "11") (pinfunction "SCK_11") (pintype "input"))
      (node (ref "IC3") (pin "11") (pinfunction "SCK_11") (pintype "input"))
      (node (ref "JP1") (pin "36") (pinfunction "36_36") (pintype "passive"))
    )
    (net (code "80") (name "REL_ST_CP") (class "Default")
      (node (ref "IC2") (pin "12") (pinfunction "RCK_12") (pintype "input"))
      (node (ref "IC3") (pin "12") (pinfunction "RCK_12") (pintype "input"))
      (node (ref "JP1") (pin "38") (pinfunction "38_38") (pintype "passive"))
    )
    (net (code "81") (name "RTS") (class "Default")
      (node (ref "IC1") (pin "2") (pinfunction "RE/_2") (pintype "input"))
      (node (ref "IC1") (pin "3") (pinfunction "DE_3") (pintype "input"))
      (node (ref "JP1") (pin "21") (pinfunction "21_21") (pintype "passive"))
    )
    (net (code "82") (name "RXD") (class "Default")
      (node (ref "IC1") (pin "1") (pinfunction "RO_1") (pintype "output"))
      (node (ref "JP1") (pin "12") (pinfunction "12_12") (pintype "passive"))
    )
    (net (code "83") (name "TXD") (class "Default")
      (node (ref "IC1") (pin "4") (pinfunction "DI_4") (pintype "input"))
      (node (ref "JP1") (pin "14") (pinfunction "14_14") (pintype "passive"))
    )
    (net (code "84") (name "VCC") (class "Default")
      (node (ref "C10") (pin "1") (pinfunction "1_1") (pintype "passive"))
      (node (ref "C11") (pin "1") (pinfunction "1_1") (pintype "passive"))
      (node (ref "C3") (pin "1") (pinfunction "1_1") (pintype "passive"))
      (node (ref "C6") (pin "1") (pinfunction "+_1") (pintype "passive"))
      (node (ref "C7") (pin "1") (pinfunction "1_1") (pintype "passive"))
      (node (ref "C8") (pin "1") (pinfunction "1_1") (pintype "passive"))
      (node (ref "C9") (pin "1") (pinfunction "1_1") (pintype "passive"))
      (node (ref "IC1") (pin "8") (pinfunction "VCC_8") (pintype "power_in"))
      (node (ref "IC2") (pin "10") (pinfunction "SCL_10") (pintype "input"))
      (node (ref "IC2") (pin "16") (pinfunction "VCC_16") (pintype "power_in"))
      (node (ref "IC3") (pin "10") (pinfunction "SCL_10") (pintype "input"))
      (node (ref "IC3") (pin "16") (pinfunction "VCC_16") (pintype "power_in"))
      (node (ref "IC4") (pin "10") (pinfunction "SCL_10") (pintype "input"))
      (node (ref "IC4") (pin "16") (pinfunction "VCC_16") (pintype "power_in"))
      (node (ref "IC5") (pin "10") (pinfunction "SCL_10") (pintype "input"))
      (node (ref "IC5") (pin "16") (pinfunction "VCC_16") (pintype "power_in"))
      (node (ref "IC6") (pin "10") (pinfunction "SCL_10") (pintype "input"))
      (node (ref "IC6") (pin "16") (pinfunction "VCC_16") (pintype "power_in"))
      (node (ref "JP3") (pin "10") (pinfunction "10_10") (pintype "passive"))
      (node (ref "JP3") (pin "9") (pinfunction "9_9") (pintype "passive"))
      (node (ref "L1") (pin "2") (pinfunction "2_2") (pintype "passive"))
      (node (ref "U1") (pin "6") (pinfunction "FB_6") (pintype "bidirectional"))
      (node (ref "X2") (pin "L1.1") (pinfunction "P1.1_L1.1") (pintype "bidirectional"))
      (node (ref "X2") (pin "L1.2") (pinfunction "P1.2_L1.2") (pintype "bidirectional"))
    )
    (net (code "85") (name "VCC3.3V") (class "Default")
      (node (ref "JP1") (pin "16") (pinfunction "16_16") (pintype "passive"))
      (node (ref "JP1") (pin "2") (pinfunction "2_2") (pintype "passive"))
      (node (ref "R8") (pin "2") (pinfunction "2_2") (pintype "passive"))
      (node (ref "R9") (pin "2") (pinfunction "2_2") (pintype "passive"))
    )
    (net (code "86") (name "VCC5V") (class "Default")
      (node (ref "JP1") (pin "1") (pinfunction "1_1") (pintype "passive"))
      (node (ref "JP1") (pin "3") (pinfunction "3_3") (pintype "passive"))
    )
    (net (code "87") (name "unconnected-(IC3A-QB-Pad1)") (class "Default")
      (node (ref "IC3") (pin "1") (pinfunction "QB_1") (pintype "tri_state"))
    )
    (net (code "88") (name "unconnected-(IC3A-QC-Pad2)") (class "Default")
      (node (ref "IC3") (pin "2") (pinfunction "QC_2") (pintype "tri_state"))
    )
    (net (code "89") (name "unconnected-(IC3A-QD-Pad3)") (class "Default")
      (node (ref "IC3") (pin "3") (pinfunction "QD_3") (pintype "tri_state"))
    )
    (net (code "90") (name "unconnected-(IC3A-QE-Pad4)") (class "Default")
      (node (ref "IC3") (pin "4") (pinfunction "QE_4") (pintype "tri_state"))
    )
    (net (code "91") (name "unconnected-(IC3A-QF-Pad5)") (class "Default")
      (node (ref "IC3") (pin "5") (pinfunction "QF_5") (pintype "tri_state"))
    )
    (net (code "92") (name "unconnected-(IC3A-QG-Pad6)") (class "Default")
      (node (ref "IC3") (pin "6") (pinfunction "QG_6") (pintype "tri_state"))
    )
    (net (code "93") (name "unconnected-(IC3A-QH*-Pad9)") (class "Default")
      (node (ref "IC3") (pin "9") (pinfunction "QH*_9") (pintype "tri_state"))
    )
    (net (code "94") (name "unconnected-(IC3A-QH-Pad7)") (class "Default")
      (node (ref "IC3") (pin "7") (pinfunction "QH_7") (pintype "tri_state"))
    )
    (net (code "95") (name "unconnected-(IC6A-QH*-Pad9)") (class "Default")
      (node (ref "IC6") (pin "9") (pinfunction "QH*_9") (pintype "tri_state"))
    )
    (net (code "96") (name "unconnected-(JP1-Pad4)") (class "Default")
      (node (ref "JP1") (pin "4") (pinfunction "4_4") (pintype "passive"))
    )
    (net (code "97") (name "unconnected-(JP1-Pad6)") (class "Default")
      (node (ref "JP1") (pin "6") (pinfunction "6_6") (pintype "passive"))
    )
    (net (code "98") (name "unconnected-(JP1-Pad7)") (class "Default")
      (node (ref "JP1") (pin "7") (pinfunction "7_7") (pintype "passive"))
    )
    (net (code "99") (name "unconnected-(JP1-Pad8)") (class "Default")
      (node (ref "JP1") (pin "8") (pinfunction "8_8") (pintype "passive"))
    )
    (net (code "100") (name "unconnected-(JP1-Pad9)") (class "Default")
      (node (ref "JP1") (pin "9") (pinfunction "9_9") (pintype "passive"))
    )
    (net (code "101") (name "unconnected-(JP1-Pad11)") (class "Default")
      (node (ref "JP1") (pin "11") (pinfunction "11_11") (pintype "passive"))
    )
    (net (code "102") (name "unconnected-(JP1-Pad18)") (class "Default")
      (node (ref "JP1") (pin "18") (pinfunction "18_18") (pintype "passive"))
    )
    (net (code "103") (name "unconnected-(JP1-Pad19)") (class "Default")
      (node (ref "JP1") (pin "19") (pinfunction "19_19") (pintype "passive"))
    )
    (net (code "104") (name "unconnected-(JP1-Pad20)") (class "Default")
      (node (ref "JP1") (pin "20") (pinfunction "20_20") (pintype "passive"))
    )
    (net (code "105") (name "unconnected-(JP1-Pad22)") (class "Default")
      (node (ref "JP1") (pin "22") (pinfunction "22_22") (pintype "passive"))
    )
    (net (code "106") (name "unconnected-(JP1-Pad23)") (class "Default")
      (node (ref "JP1") (pin "23") (pinfunction "23_23") (pintype "passive"))
    )
    (net (code "107") (name "unconnected-(JP1-Pad24)") (class "Default")
      (node (ref "JP1") (pin "24") (pinfunction "24_24") (pintype "passive"))
    )
    (net (code "108") (name "unconnected-(JP1-Pad25)") (class "Default")
      (node (ref "JP1") (pin "25") (pinfunction "25_25") (pintype "passive"))
    )
    (net (code "109") (name "unconnected-(JP1-Pad27)") (class "Default")
      (node (ref "JP1") (pin "27") (pinfunction "27_27") (pintype "passive"))
    )
    (net (code "110") (name "unconnected-(JP1-Pad28)") (class "Default")
      (node (ref "JP1") (pin "28") (pinfunction "28_28") (pintype "passive"))
    )
    (net (code "111") (name "unconnected-(JP1-Pad29)") (class "Default")
      (node (ref "JP1") (pin "29") (pinfunction "29_29") (pintype "passive"))
    )
    (net (code "112") (name "unconnected-(JP1-Pad30)") (class "Default")
      (node (ref "JP1") (pin "30") (pinfunction "30_30") (pintype "passive"))
    )
    (net (code "113") (name "unconnected-(JP3-Pad12)") (class "Default")
      (node (ref "JP3") (pin "12") (pinfunction "12_12") (pintype "passive"))
    )
    (net (code "114") (name "unconnected-(JP3-Pad14)") (class "Default")
      (node (ref "JP3") (pin "14") (pinfunction "14_14") (pintype "passive"))
    )
    (net (code "115") (name "unconnected-(JP3-Pad16)") (class "Default")
      (node (ref "JP3") (pin "16") (pinfunction "16_16") (pintype "passive"))
    )
    (net (code "116") (name "unconnected-(JP3-Pad17)") (class "Default")
      (node (ref "JP3") (pin "17") (pinfunction "17_17") (pintype "passive"))
    )
    (net (code "117") (name "unconnected-(JP3-Pad18)") (class "Default")
      (node (ref "JP3") (pin "18") (pinfunction "18_18") (pintype "passive"))
    )
    (net (code "118") (name "unconnected-(U1-EN-Pad7)") (class "Default")
      (node (ref "U1") (pin "7") (pinfunction "EN_7") (pintype "bidirectional"))
    )
    (net (code "119") (name "unconnected-(U1-NC-Pad5)") (class "Default")
      (node (ref "U1") (pin "5") (pinfunction "NC_5") (pintype "no_connect"))
    )
  )
)
